# CH32LoongsonEJTAG_v1_2.net
KiCad netlist of a schematic drawn in EasyEDA Pro
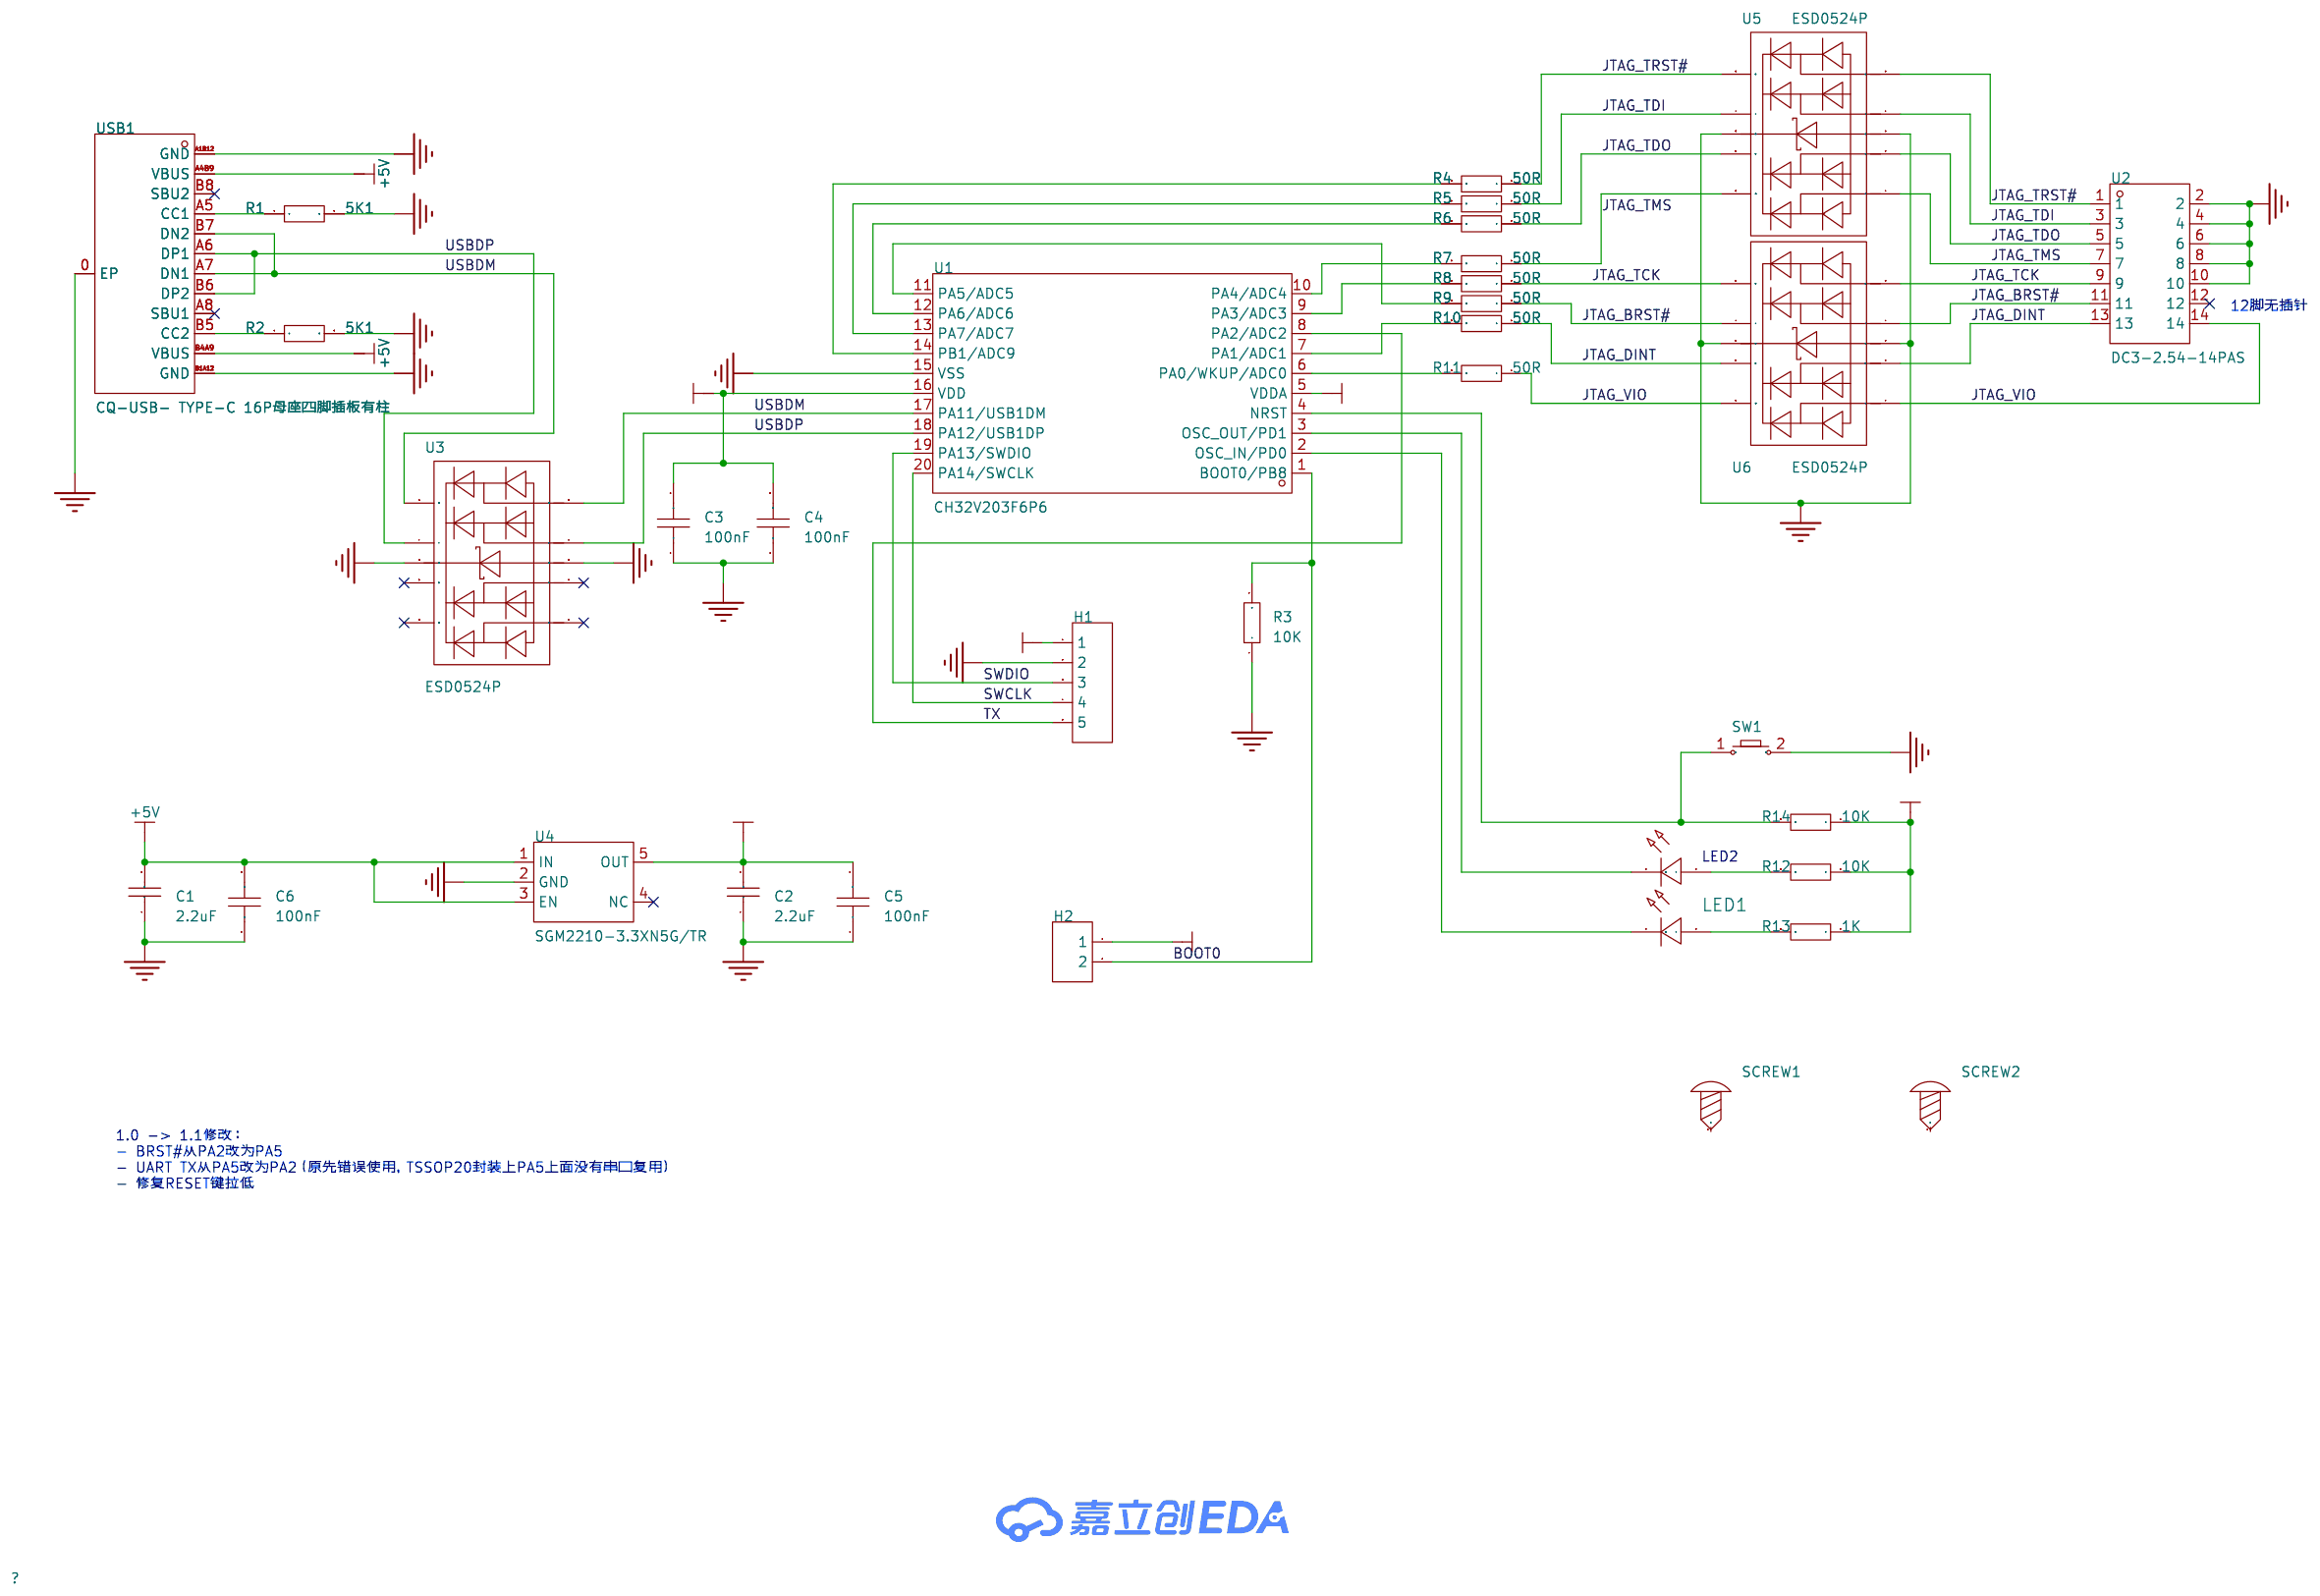
[diagram p0: schematic sheet]

(export (version "E")
  (design (tool "Eeschema 10.0.6"))
  (components
    (comp (ref "C1")
      (value "2.2uF")
      (footprint "easyedapro:C1206")
      (description "容值:4.7uF;精度:±10%;额定电压:50V;温度系数:X7R;")
      (fields (field (name "Manufacturer Part") "0603B222K500NT") (field (name "Manufacturer") "FH(风华)"))
      (libsource (lib "easyedapro") (part "1206B475K500NT"))
    )
    (comp (ref "C2")
      (value "2.2uF")
      (footprint "easyedapro:C1206")
      (description "容值:4.7uF;精度:±10%;额定电压:50V;温度系数:X7R;")
      (fields (field (name "Manufacturer Part") "0603B222K500NT") (field (name "Manufacturer") "FH(风华)"))
      (libsource (lib "easyedapro") (part "1206B475K500NT"))
    )
    (comp (ref "C3")
      (value "100nF")
      (footprint "easyedapro:C0603")
      (description "容值:100nF;精度:±10%;额定电压:50V;材质(温度系数):X7R;")
      (fields
        (field (name "Manufacturer Part") "CC0603KRX7R9BB104")
        (field (name "Manufacturer") "YAGEO(国巨)")
      )
      (libsource (lib "easyedapro") (part "CC0603KRX7R9BB104"))
    )
    (comp (ref "C4")
      (value "100nF")
      (footprint "easyedapro:C0603")
      (description "容值:100nF;精度:±10%;额定电压:50V;材质(温度系数):X7R;")
      (fields
        (field (name "Manufacturer Part") "CC0603KRX7R9BB104")
        (field (name "Manufacturer") "YAGEO(国巨)")
      )
      (libsource (lib "easyedapro") (part "CC0603KRX7R9BB104"))
    )
    (comp (ref "C5")
      (value "100nF")
      (footprint "easyedapro:C0603")
      (description "容值:100nF;精度:±10%;额定电压:50V;材质(温度系数):X7R;")
      (fields
        (field (name "Manufacturer Part") "CC0603KRX7R9BB104")
        (field (name "Manufacturer") "YAGEO(国巨)")
      )
      (libsource (lib "easyedapro") (part "CC0603KRX7R9BB104"))
    )
    (comp (ref "C6")
      (value "100nF")
      (footprint "easyedapro:C0603")
      (description "容值:100nF;精度:±10%;额定电压:50V;材质(温度系数):X7R;")
      (fields
        (field (name "Manufacturer Part") "CC0603KRX7R9BB104")
        (field (name "Manufacturer") "YAGEO(国巨)")
      )
      (libsource (lib "easyedapro") (part "CC0603KRX7R9BB104"))
    )
    (comp (ref "H1")
      (value "~")
      (footprint "easyedapro:HDR-TH_5P-P2.54-V-F")
      (libsource (lib "easyedapro") (part "Header-Female-2.54_1x5"))
    )
    (comp (ref "H2")
      (value "~")
      (footprint "easyedapro:HDR-TH_2P-P2.54-V-F")
      (libsource (lib "easyedapro") (part "Header-Female-2.54_1x2"))
    )
    (comp (ref "LED1")
      (value "~")
      (footprint "easyedapro:LED_0603")
      (libsource (lib "easyedapro") (part "LED_R"))
    )
    (comp (ref "LED2")
      (value "~")
      (footprint "easyedapro:LED_0603")
      (libsource (lib "easyedapro") (part "LED_G"))
    )
    (comp (ref "R1") (value "5K1") (footprint "easyedapro:R0603") (libsource (lib "easyedapro") (part "电阻")))
    (comp (ref "R2") (value "5K1") (footprint "easyedapro:R0603") (libsource (lib "easyedapro") (part "电阻")))
    (comp (ref "R3") (value "10K") (footprint "easyedapro:R0603") (libsource (lib "easyedapro") (part "电阻")))
    (comp (ref "R4") (value "50R") (footprint "easyedapro:R0603") (libsource (lib "easyedapro") (part "电阻")))
    (comp (ref "R5") (value "50R") (footprint "easyedapro:R0603") (libsource (lib "easyedapro") (part "电阻")))
    (comp (ref "R6") (value "50R") (footprint "easyedapro:R0603") (libsource (lib "easyedapro") (part "电阻")))
    (comp (ref "R7") (value "50R") (footprint "easyedapro:R0603") (libsource (lib "easyedapro") (part "电阻")))
    (comp (ref "R8") (value "50R") (footprint "easyedapro:R0603") (libsource (lib "easyedapro") (part "电阻")))
    (comp (ref "R9") (value "50R") (footprint "easyedapro:R0603") (libsource (lib "easyedapro") (part "电阻")))
    (comp (ref "R10") (value "50R") (footprint "easyedapro:R0603") (libsource (lib "easyedapro") (part "电阻")))
    (comp (ref "R11") (value "50R") (footprint "easyedapro:R0603") (libsource (lib "easyedapro") (part "电阻")))
    (comp (ref "R12") (value "10K") (footprint "easyedapro:R0603") (libsource (lib "easyedapro") (part "电阻")))
    (comp (ref "R13") (value "1K") (footprint "easyedapro:R0603") (libsource (lib "easyedapro") (part "电阻")))
    (comp (ref "R14") (value "10K") (footprint "easyedapro:R0603") (libsource (lib "easyedapro") (part "电阻")))
    (comp (ref "SCREW1")
      (value "~")
      (footprint "easyedapro:M2螺丝")
      (libsource (lib "easyedapro") (part "螺丝孔"))
    )
    (comp (ref "SCREW2")
      (value "~")
      (footprint "easyedapro:M2螺丝")
      (libsource (lib "easyedapro") (part "螺丝孔"))
    )
    (comp (ref "SW1")
      (value "~")
      (footprint "easyedapro:Key_SMD_3x4x2")
      (libsource (lib "easyedapro") (part "轻触按键x2"))
    )
    (comp (ref "U1")
      (value "CH32V203F6P6")
      (footprint "easyedapro:TSSOP-20_L6.5-W4.4-P0.65-LS6.4-BL")
      (fields (field (name "Manufacturer") "WCH(南京沁恒)"))
      (libsource (lib "easyedapro") (part "CH32V203F6P6"))
    )
    (comp (ref "U2")
      (value "DC3-2.54-14PAS")
      (footprint "easyedapro:IDC-TH_14P-P2.54_DC3-2.54-14PAS")
      (description "连接器类型:简牛座;间距:2.54mm;结构:2x7P;额定电流:1.5A;额定电压:-;封装形式:直插;行距:2.54mm;排数:2;每排PIN数:7;工作温度范围:-40°C~+105°C;")
      (fields (field (name "Manufacturer") "ZHOURI(洲日)"))
      (libsource (lib "easyedapro") (part "DC3-2.54-14PAS"))
    )
    (comp (ref "U3")
      (value "ESD0524P")
      (footprint "easyedapro:DFN-10_L2.5-W1.0-P0.50-BL-A")
      (description "极性:单向;反向截止电压(Vrwm):5V;最大钳位电压:15V;峰值脉冲电流(Ipp)@10/1000us:2A;峰值脉冲功率(Ppp)@10/1000us:-;击穿电压:6V;")
      (fields (field (name "Manufacturer") "SHIKUES(时科)"))
      (libsource (lib "easyedapro") (part "ESD0524P_C5334573"))
    )
    (comp (ref "U4")
      (value "SGM2210-3.3XN5G/TR")
      (footprint "easyedapro:SOT-23-5_L2.9-W1.6-P0.95-LS2.8-BL")
      (description "输出类型:固定;工作电压:20V;输出电压:3.3V;输出电流:300mA;电源纹波抑制比(PSRR):100dB@(1kHz);输出极性:正极;")
      (fields (field (name "Manufacturer") "SGMICRO(圣邦微)"))
      (libsource (lib "easyedapro") (part "SGM2210-3.3XN5G/TR"))
    )
    (comp (ref "U5")
      (value "ESD0524P")
      (footprint "easyedapro:DFN-10_L2.5-W1.0-P0.50-BL-A")
      (description "极性:单向;反向截止电压(Vrwm):5V;最大钳位电压:15V;峰值脉冲电流(Ipp)@10/1000us:2A;峰值脉冲功率(Ppp)@10/1000us:-;击穿电压:6V;")
      (fields (field (name "Manufacturer") "SHIKUES(时科)"))
      (libsource (lib "easyedapro") (part "ESD0524P_C5334573"))
    )
    (comp (ref "U6")
      (value "ESD0524P")
      (footprint "easyedapro:DFN-10_L2.5-W1.0-P0.50-BL-A")
      (description "极性:单向;反向截止电压(Vrwm):5V;最大钳位电压:15V;峰值脉冲电流(Ipp)@10/1000us:2A;峰值脉冲功率(Ppp)@10/1000us:-;击穿电压:6V;")
      (fields (field (name "Manufacturer") "SHIKUES(时科)"))
      (libsource (lib "easyedapro") (part "ESD0524P_C5334573"))
    )
    (comp (ref "USB1")
      (value "CQ-USB- TYPE-C 16P母座四脚插板有柱")
      (footprint "easyedapro:USB-C-SMD_CQ-USB-TYPE-C")
      (libsource (lib "easyedapro") (part "CQ-USB- TYPE-C 16P母座四脚插板有柱"))
    )
  )
  (nets
    (net (code "1") (name "+3V3") (class "Default")
      (node (ref "C2") (pin "2") (pinfunction "2_2") (pintype "input"))
      (node (ref "C3") (pin "2") (pinfunction "2_2") (pintype "unspecified"))
      (node (ref "C4") (pin "2") (pinfunction "2_2") (pintype "unspecified"))
      (node (ref "C5") (pin "2") (pinfunction "2_2") (pintype "unspecified"))
      (node (ref "H1") (pin "1") (pinfunction "1_1") (pintype "input"))
      (node (ref "H2") (pin "1") (pinfunction "1_1") (pintype "input"))
      (node (ref "R12") (pin "1") (pinfunction "1_1") (pintype "input"))
      (node (ref "R13") (pin "1") (pinfunction "1_1") (pintype "input"))
      (node (ref "R14") (pin "1") (pinfunction "1_1") (pintype "input"))
      (node (ref "U1") (pin "16") (pinfunction "VDD_16") (pintype "unspecified"))
      (node (ref "U1") (pin "5") (pinfunction "VDDA_5") (pintype "unspecified"))
      (node (ref "U4") (pin "5") (pinfunction "OUT_5") (pintype "unspecified"))
    )
    (net (code "2") (name "+5V") (class "Default")
      (node (ref "C1") (pin "2") (pinfunction "2_2") (pintype "input"))
      (node (ref "C6") (pin "2") (pinfunction "2_2") (pintype "unspecified"))
      (node (ref "U4") (pin "1") (pinfunction "IN_1") (pintype "unspecified"))
      (node (ref "U4") (pin "3") (pinfunction "EN_3") (pintype "unspecified"))
      (node (ref "USB1") (pin "A4B9") (pinfunction "VBUS_A4B9") (pintype "unspecified"))
      (node (ref "USB1") (pin "B4A9") (pinfunction "VBUS_B4A9") (pintype "unspecified"))
    )
    (net (code "3") (name "/BOOT0") (class "Default")
      (node (ref "H2") (pin "2") (pinfunction "2_2") (pintype "input"))
      (node (ref "R3") (pin "2") (pinfunction "2_2") (pintype "input"))
      (node (ref "U1") (pin "1") (pinfunction "BOOT0/PB8_1") (pintype "unspecified"))
    )
    (net (code "4") (name "/JTAG_BRST#") (class "Default")
      (node (ref "R9") (pin "1") (pinfunction "1_1") (pintype "input"))
      (node (ref "U2") (pin "11") (pinfunction "11_11") (pintype "unspecified"))
      (node (ref "U6") (pin "4") (pinfunction "4_4") (pintype "unspecified"))
      (node (ref "U6") (pin "7") (pinfunction "7_7") (pintype "unspecified"))
    )
    (net (code "5") (name "/JTAG_DINT") (class "Default")
      (node (ref "R10") (pin "1") (pinfunction "1_1") (pintype "input"))
      (node (ref "U2") (pin "13") (pinfunction "13_13") (pintype "unspecified"))
      (node (ref "U6") (pin "2") (pinfunction "2_2") (pintype "unspecified"))
      (node (ref "U6") (pin "9") (pinfunction "9_9") (pintype "unspecified"))
    )
    (net (code "6") (name "/JTAG_TCK") (class "Default")
      (node (ref "R8") (pin "1") (pinfunction "1_1") (pintype "input"))
      (node (ref "U2") (pin "9") (pinfunction "9_9") (pintype "unspecified"))
      (node (ref "U6") (pin "5") (pinfunction "5_5") (pintype "unspecified"))
      (node (ref "U6") (pin "6") (pinfunction "6_6") (pintype "unspecified"))
    )
    (net (code "7") (name "/JTAG_TDI") (class "Default")
      (node (ref "R5") (pin "1") (pinfunction "1_1") (pintype "input"))
      (node (ref "U2") (pin "3") (pinfunction "3_3") (pintype "unspecified"))
      (node (ref "U5") (pin "4") (pinfunction "4_4") (pintype "unspecified"))
      (node (ref "U5") (pin "7") (pinfunction "7_7") (pintype "unspecified"))
    )
    (net (code "8") (name "/JTAG_TDO") (class "Default")
      (node (ref "R6") (pin "1") (pinfunction "1_1") (pintype "input"))
      (node (ref "U2") (pin "5") (pinfunction "5_5") (pintype "unspecified"))
      (node (ref "U5") (pin "2") (pinfunction "2_2") (pintype "unspecified"))
      (node (ref "U5") (pin "9") (pinfunction "9_9") (pintype "unspecified"))
    )
    (net (code "9") (name "/JTAG_TMS") (class "Default")
      (node (ref "R7") (pin "1") (pinfunction "1_1") (pintype "input"))
      (node (ref "U2") (pin "7") (pinfunction "7_7") (pintype "unspecified"))
      (node (ref "U5") (pin "1") (pinfunction "1_1") (pintype "unspecified"))
      (node (ref "U5") (pin "10") (pinfunction "10_10") (pintype "unspecified"))
    )
    (net (code "10") (name "/JTAG_TRST#") (class "Default")
      (node (ref "R4") (pin "1") (pinfunction "1_1") (pintype "input"))
      (node (ref "U2") (pin "1") (pinfunction "1_1") (pintype "unspecified"))
      (node (ref "U5") (pin "5") (pinfunction "5_5") (pintype "unspecified"))
      (node (ref "U5") (pin "6") (pinfunction "6_6") (pintype "unspecified"))
    )
    (net (code "11") (name "/JTAG_VIO") (class "Default")
      (node (ref "R11") (pin "1") (pinfunction "1_1") (pintype "input"))
      (node (ref "U2") (pin "14") (pinfunction "14_14") (pintype "unspecified"))
      (node (ref "U6") (pin "1") (pinfunction "1_1") (pintype "unspecified"))
      (node (ref "U6") (pin "10") (pinfunction "10_10") (pintype "unspecified"))
    )
    (net (code "12") (name "/SWCLK") (class "Default")
      (node (ref "H1") (pin "4") (pinfunction "4_4") (pintype "input"))
      (node (ref "U1") (pin "20") (pinfunction "PA14/SWCLK_20") (pintype "unspecified"))
    )
    (net (code "13") (name "/SWDIO") (class "Default")
      (node (ref "H1") (pin "3") (pinfunction "3_3") (pintype "input"))
      (node (ref "U1") (pin "19") (pinfunction "PA13/SWDIO_19") (pintype "unspecified"))
    )
    (net (code "14") (name "/TX") (class "Default")
      (node (ref "H1") (pin "5") (pinfunction "5_5") (pintype "input"))
      (node (ref "U1") (pin "8") (pinfunction "PA2/ADC2_8") (pintype "unspecified"))
    )
    (net (code "15") (name "/USBDM") (class "Default")
      (node (ref "U1") (pin "17") (pinfunction "PA11/USB1DM_17") (pintype "unspecified"))
      (node (ref "U3") (pin "5") (pinfunction "5_5") (pintype "unspecified"))
      (node (ref "U3") (pin "6") (pinfunction "6_6") (pintype "unspecified"))
      (node (ref "USB1") (pin "A7") (pinfunction "DN1_A7") (pintype "unspecified"))
      (node (ref "USB1") (pin "B7") (pinfunction "DN2_B7") (pintype "unspecified"))
    )
    (net (code "16") (name "/USBDP") (class "Default")
      (node (ref "U1") (pin "18") (pinfunction "PA12/USB1DP_18") (pintype "unspecified"))
      (node (ref "U3") (pin "4") (pinfunction "4_4") (pintype "unspecified"))
      (node (ref "U3") (pin "7") (pinfunction "7_7") (pintype "unspecified"))
      (node (ref "USB1") (pin "A6") (pinfunction "DP1_A6") (pintype "unspecified"))
      (node (ref "USB1") (pin "B6") (pinfunction "DP2_B6") (pintype "unspecified"))
    )
    (net (code "17") (name "GND") (class "Default")
      (node (ref "C1") (pin "1") (pinfunction "1_1") (pintype "input"))
      (node (ref "C2") (pin "1") (pinfunction "1_1") (pintype "input"))
      (node (ref "C3") (pin "1") (pinfunction "1_1") (pintype "unspecified"))
      (node (ref "C4") (pin "1") (pinfunction "1_1") (pintype "unspecified"))
      (node (ref "C5") (pin "1") (pinfunction "1_1") (pintype "unspecified"))
      (node (ref "C6") (pin "1") (pinfunction "1_1") (pintype "unspecified"))
      (node (ref "H1") (pin "2") (pinfunction "2_2") (pintype "input"))
      (node (ref "R1") (pin "2") (pinfunction "2_2") (pintype "input"))
      (node (ref "R2") (pin "2") (pinfunction "2_2") (pintype "input"))
      (node (ref "R3") (pin "1") (pinfunction "1_1") (pintype "input"))
      (node (ref "SW1") (pin "2") (pinfunction "2_2") (pintype "input"))
      (node (ref "U1") (pin "15") (pinfunction "VSS_15") (pintype "unspecified"))
      (node (ref "U2") (pin "10") (pinfunction "10_10") (pintype "unspecified"))
      (node (ref "U2") (pin "2") (pinfunction "2_2") (pintype "unspecified"))
      (node (ref "U2") (pin "4") (pinfunction "4_4") (pintype "unspecified"))
      (node (ref "U2") (pin "6") (pinfunction "6_6") (pintype "unspecified"))
      (node (ref "U2") (pin "8") (pinfunction "8_8") (pintype "unspecified"))
      (node (ref "U3") (pin "3") (pinfunction "3_3") (pintype "unspecified"))
      (node (ref "U3") (pin "8") (pinfunction "8_8") (pintype "unspecified"))
      (node (ref "U4") (pin "2") (pinfunction "GND_2") (pintype "unspecified"))
      (node (ref "U5") (pin "3") (pinfunction "3_3") (pintype "unspecified"))
      (node (ref "U5") (pin "8") (pinfunction "8_8") (pintype "unspecified"))
      (node (ref "U6") (pin "3") (pinfunction "3_3") (pintype "unspecified"))
      (node (ref "U6") (pin "8") (pinfunction "8_8") (pintype "unspecified"))
      (node (ref "USB1") (pin "0") (pinfunction "EP_0") (pintype "unspecified"))
      (node (ref "USB1") (pin "A1B12") (pinfunction "GND_A1B12") (pintype "unspecified"))
      (node (ref "USB1") (pin "B1A12") (pinfunction "GND_B1A12") (pintype "unspecified"))
    )
    (net (code "18") (name "Net-(LED1-A)") (class "Default")
      (node (ref "LED1") (pin "2") (pinfunction "A_2") (pintype "input"))
      (node (ref "R13") (pin "2") (pinfunction "2_2") (pintype "input"))
    )
    (net (code "19") (name "Net-(LED1-C)") (class "Default")
      (node (ref "LED1") (pin "1") (pinfunction "C_1") (pintype "input"))
      (node (ref "U1") (pin "2") (pinfunction "OSC_IN/PD0_2") (pintype "unspecified"))
    )
    (net (code "20") (name "Net-(LED2-A)") (class "Default")
      (node (ref "LED2") (pin "2") (pinfunction "A_2") (pintype "input"))
      (node (ref "R12") (pin "2") (pinfunction "2_2") (pintype "input"))
    )
    (net (code "21") (name "Net-(LED2-C)") (class "Default")
      (node (ref "LED2") (pin "1") (pinfunction "C_1") (pintype "input"))
      (node (ref "U1") (pin "3") (pinfunction "OSC_OUT/PD1_3") (pintype "unspecified"))
    )
    (net (code "22") (name "Net-(U1-NRST)") (class "Default")
      (node (ref "R14") (pin "2") (pinfunction "2_2") (pintype "input"))
      (node (ref "SW1") (pin "1") (pinfunction "1_1") (pintype "input"))
      (node (ref "U1") (pin "4") (pinfunction "NRST_4") (pintype "unspecified"))
    )
    (net (code "23") (name "Net-(U1-PA0{slash}WKUP{slash}ADC0)") (class "Default")
      (node (ref "R11") (pin "2") (pinfunction "2_2") (pintype "input"))
      (node (ref "U1") (pin "6") (pinfunction "PA0/WKUP/ADC0_6") (pintype "unspecified"))
    )
    (net (code "24") (name "Net-(U1-PA1{slash}ADC1)") (class "Default")
      (node (ref "R10") (pin "2") (pinfunction "2_2") (pintype "input"))
      (node (ref "U1") (pin "7") (pinfunction "PA1/ADC1_7") (pintype "unspecified"))
    )
    (net (code "25") (name "Net-(U1-PA3{slash}ADC3)") (class "Default")
      (node (ref "R8") (pin "2") (pinfunction "2_2") (pintype "input"))
      (node (ref "U1") (pin "9") (pinfunction "PA3/ADC3_9") (pintype "unspecified"))
    )
    (net (code "26") (name "Net-(U1-PA4{slash}ADC4)") (class "Default")
      (node (ref "R7") (pin "2") (pinfunction "2_2") (pintype "input"))
      (node (ref "U1") (pin "10") (pinfunction "PA4/ADC4_10") (pintype "unspecified"))
    )
    (net (code "27") (name "Net-(U1-PA5{slash}ADC5)") (class "Default")
      (node (ref "R9") (pin "2") (pinfunction "2_2") (pintype "input"))
      (node (ref "U1") (pin "11") (pinfunction "PA5/ADC5_11") (pintype "unspecified"))
    )
    (net (code "28") (name "Net-(U1-PA6{slash}ADC6)") (class "Default")
      (node (ref "R6") (pin "2") (pinfunction "2_2") (pintype "input"))
      (node (ref "U1") (pin "12") (pinfunction "PA6/ADC6_12") (pintype "unspecified"))
    )
    (net (code "29") (name "Net-(U1-PA7{slash}ADC7)") (class "Default")
      (node (ref "R5") (pin "2") (pinfunction "2_2") (pintype "input"))
      (node (ref "U1") (pin "13") (pinfunction "PA7/ADC7_13") (pintype "unspecified"))
    )
    (net (code "30") (name "Net-(U1-PB1{slash}ADC9)") (class "Default")
      (node (ref "R4") (pin "2") (pinfunction "2_2") (pintype "input"))
      (node (ref "U1") (pin "14") (pinfunction "PB1/ADC9_14") (pintype "unspecified"))
    )
    (net (code "31") (name "Net-(USB1-CC1)") (class "Default")
      (node (ref "R1") (pin "1") (pinfunction "1_1") (pintype "input"))
      (node (ref "USB1") (pin "A5") (pinfunction "CC1_A5") (pintype "unspecified"))
    )
    (net (code "32") (name "Net-(USB1-CC2)") (class "Default")
      (node (ref "R2") (pin "1") (pinfunction "1_1") (pintype "input"))
      (node (ref "USB1") (pin "B5") (pinfunction "CC2_B5") (pintype "unspecified"))
    )
    (net (code "33") (name "unconnected-(SCREW1-Pad1)") (class "Default")
      (node (ref "SCREW1") (pin "1") (pinfunction "1_1") (pintype "input"))
    )
    (net (code "34") (name "unconnected-(SCREW2-Pad1)") (class "Default")
      (node (ref "SCREW2") (pin "1") (pinfunction "1_1") (pintype "input"))
    )
    (net (code "35") (name "unconnected-(U2-Pad12)") (class "Default")
      (node (ref "U2") (pin "12") (pinfunction "12_12") (pintype "unspecified+no_connect"))
    )
    (net (code "36") (name "unconnected-(U3-Pad1)") (class "Default")
      (node (ref "U3") (pin "1") (pinfunction "1_1") (pintype "unspecified+no_connect"))
    )
    (net (code "37") (name "unconnected-(U3-Pad2)") (class "Default")
      (node (ref "U3") (pin "2") (pinfunction "2_2") (pintype "unspecified+no_connect"))
    )
    (net (code "38") (name "unconnected-(U3-Pad9)") (class "Default")
      (node (ref "U3") (pin "9") (pinfunction "9_9") (pintype "unspecified+no_connect"))
    )
    (net (code "39") (name "unconnected-(U3-Pad10)") (class "Default")
      (node (ref "U3") (pin "10") (pinfunction "10_10") (pintype "unspecified+no_connect"))
    )
    (net (code "40") (name "unconnected-(U4-NC-Pad4)") (class "Default")
      (node (ref "U4") (pin "4") (pinfunction "NC_4") (pintype "unspecified+no_connect"))
    )
    (net (code "41") (name "unconnected-(USB1-SBU1-PadA8)") (class "Default")
      (node (ref "USB1") (pin "A8") (pinfunction "SBU1_A8") (pintype "unspecified+no_connect"))
    )
    (net (code "42") (name "unconnected-(USB1-SBU2-PadB8)") (class "Default")
      (node (ref "USB1") (pin "B8") (pinfunction "SBU2_B8") (pintype "unspecified+no_connect"))
    )
  )
)
